# DualMonoPSU3.net
KiCad netlist of a schematic drawn in EAGLE
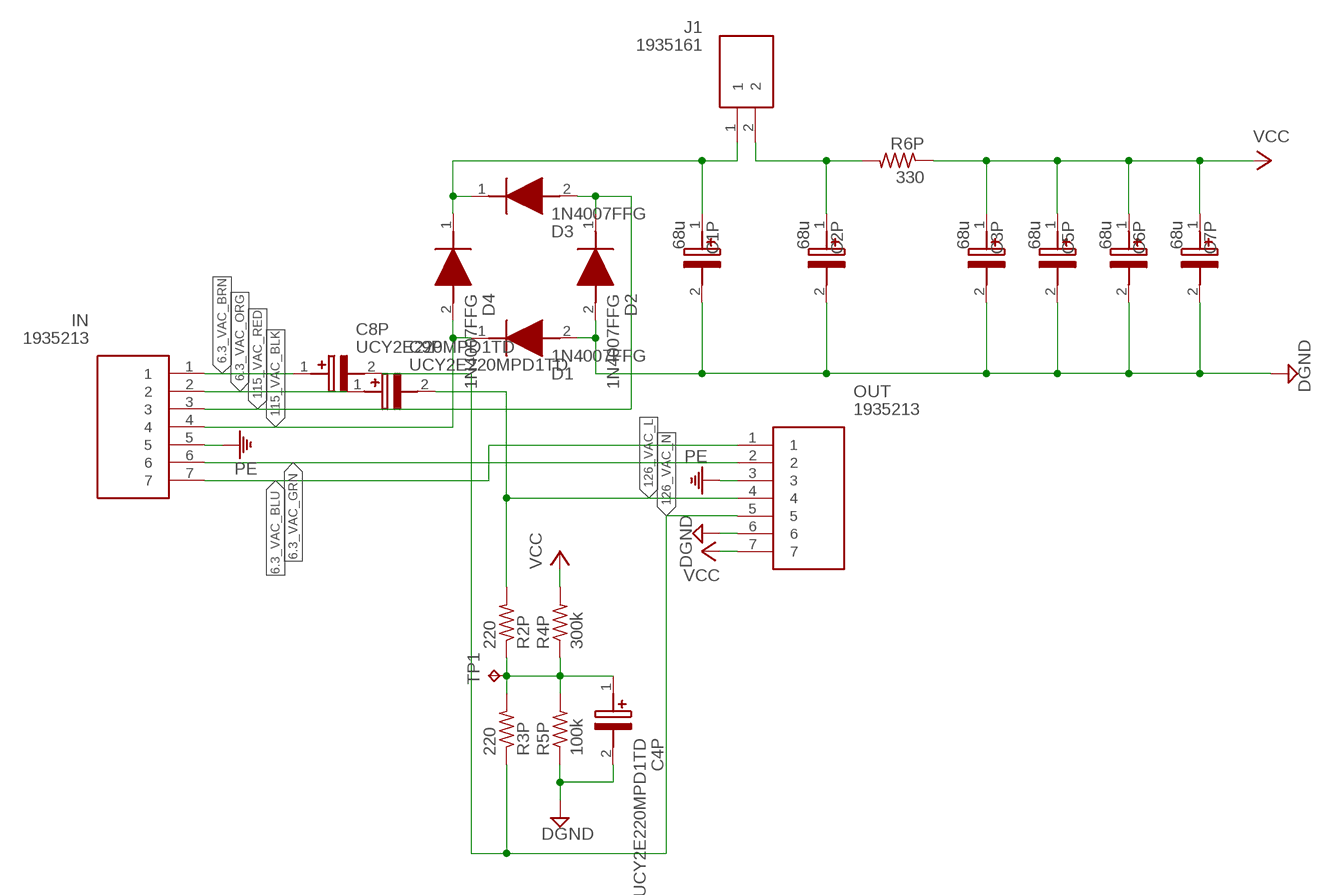
[diagram p0: schematic, sheet 1]

(export (version "E")
  (design (tool "Eeschema 10.0.6"))
  (components
    (comp (ref "C1P")
      (value "68u")
      (footprint "eagle-import:CAPPRD750W80D1475H4700")
      (fields (field (name "MANUFACTURER_PART_NUMBER") "500HXW68MEFR14.5X45"))
      (libsource (lib "eagle-import") (part "500HXW68MEFR14.5X45"))
    )
    (comp (ref "C2P")
      (value "68u")
      (footprint "eagle-import:CAPPRD750W80D1475H4700")
      (fields (field (name "MANUFACTURER_PART_NUMBER") "500HXW68MEFR14.5X45"))
      (libsource (lib "eagle-import") (part "500HXW68MEFR14.5X45"))
    )
    (comp (ref "C3P")
      (value "68u")
      (footprint "eagle-import:CAPPRD750W80D1475H4700")
      (fields (field (name "MANUFACTURER_PART_NUMBER") "500HXW68MEFR14.5X45"))
      (libsource (lib "eagle-import") (part "500HXW68MEFR14.5X45"))
    )
    (comp (ref "C4P")
      (value "UCY2E220MPD1TD")
      (footprint "eagle-import:CAPPRD500W60D1025H1750")
      (fields (field (name "MOUSER_PART_NUMBER") "647-UCY2E220MPD1TD"))
      (libsource (lib "eagle-import") (part "UCY2E220MPD1TD"))
    )
    (comp (ref "C5P")
      (value "68u")
      (footprint "eagle-import:CAPPRD750W80D1475H4700")
      (fields (field (name "MANUFACTURER_PART_NUMBER") "500HXW68MEFR14.5X45"))
      (libsource (lib "eagle-import") (part "500HXW68MEFR14.5X45"))
    )
    (comp (ref "C6P")
      (value "68u")
      (footprint "eagle-import:CAPPRD750W80D1475H4700")
      (fields (field (name "MANUFACTURER_PART_NUMBER") "500HXW68MEFR14.5X45"))
      (libsource (lib "eagle-import") (part "500HXW68MEFR14.5X45"))
    )
    (comp (ref "C7P")
      (value "68u")
      (footprint "eagle-import:CAPPRD750W80D1475H4700")
      (fields (field (name "MANUFACTURER_PART_NUMBER") "500HXW68MEFR14.5X45"))
      (libsource (lib "eagle-import") (part "500HXW68MEFR14.5X45"))
    )
    (comp (ref "C8P")
      (value "UCY2E220MPD1TD")
      (footprint "eagle-import:CAPPRD500W60D1025H1750")
      (fields (field (name "MOUSER_PART_NUMBER") "647-UCY2E220MPD1TD"))
      (libsource (lib "eagle-import") (part "UCY2E220MPD1TD"))
    )
    (comp (ref "C9P")
      (value "UCY2E220MPD1TD")
      (footprint "eagle-import:CAPPRD500W60D1025H1750")
      (fields (field (name "MOUSER_PART_NUMBER") "647-UCY2E220MPD1TD"))
      (libsource (lib "eagle-import") (part "UCY2E220MPD1TD"))
    )
    (comp (ref "D1")
      (value "1N4007FFG")
      (footprint "eagle-import:DIOAD1405W86L465D235")
      (fields (field (name "MOUSER_PART_NUMBER") "863-1N4007FFG"))
      (libsource (lib "eagle-import") (part "1N4007FFG"))
    )
    (comp (ref "D2")
      (value "1N4007FFG")
      (footprint "eagle-import:DIOAD1405W86L465D235")
      (fields (field (name "MOUSER_PART_NUMBER") "863-1N4007FFG"))
      (libsource (lib "eagle-import") (part "1N4007FFG"))
    )
    (comp (ref "D3")
      (value "1N4007FFG")
      (footprint "eagle-import:DIOAD1405W86L465D235")
      (fields (field (name "MOUSER_PART_NUMBER") "863-1N4007FFG"))
      (libsource (lib "eagle-import") (part "1N4007FFG"))
    )
    (comp (ref "D4")
      (value "1N4007FFG")
      (footprint "eagle-import:DIOAD1405W86L465D235")
      (fields (field (name "MOUSER_PART_NUMBER") "863-1N4007FFG"))
      (libsource (lib "eagle-import") (part "1N4007FFG"))
    )
    (comp (ref "IN")
      (value "1935213")
      (footprint "eagle-import:1935213")
      (fields (field (name "MOUSER_PART_NUMBER") "651-1935213"))
      (libsource (lib "eagle-import") (part "1935213"))
    )
    (comp (ref "J1")
      (value "1935161")
      (footprint "eagle-import:1935161")
      (fields (field (name "MOUSER_PART_NUMBER") "651-1935161"))
      (libsource (lib "eagle-import") (part "1935161"))
    )
    (comp (ref "OUT")
      (value "1935213")
      (footprint "eagle-import:1935213")
      (fields (field (name "MOUSER_PART_NUMBER") "651-1935213"))
      (libsource (lib "eagle-import") (part "1935213"))
    )
    (comp (ref "R2P")
      (value "220")
      (footprint "eagle-import:0411_15")
      (libsource (lib "eagle-import") (part "R-US_0411/15"))
    )
    (comp (ref "R3P")
      (value "220")
      (footprint "eagle-import:0411_15")
      (libsource (lib "eagle-import") (part "R-US_0411/15"))
    )
    (comp (ref "R4P")
      (value "300k")
      (footprint "eagle-import:0411_15")
      (libsource (lib "eagle-import") (part "R-US_0411/15"))
    )
    (comp (ref "R5P")
      (value "100k")
      (footprint "eagle-import:0411_15")
      (libsource (lib "eagle-import") (part "R-US_0411/15"))
    )
    (comp (ref "R6P")
      (value "330")
      (footprint "eagle-import:0411_15")
      (libsource (lib "eagle-import") (part "R-US_0411/15"))
    )
    (comp (ref "TP1")
      (value "TPB2,54")
      (footprint "eagle-import:B2,54")
      (libsource (lib "eagle-import") (part "TPB2,54"))
    )
  )
  (nets
    (net (code "1") (name "6.3_VAC_BLU") (class "Default")
      (node (ref "IN") (pin "7") (pinfunction "7_7") (pintype "bidirectional"))
      (node (ref "OUT") (pin "1") (pinfunction "1_1") (pintype "bidirectional"))
    )
    (net (code "2") (name "6.3_VAC_BRN") (class "Default")
      (node (ref "C8P") (pin "1") (pinfunction "+_1") (pintype "bidirectional"))
      (node (ref "IN") (pin "1") (pinfunction "1_1") (pintype "bidirectional"))
    )
    (net (code "3") (name "6.3_VAC_GRN") (class "Default")
      (node (ref "IN") (pin "6") (pinfunction "6_6") (pintype "bidirectional"))
      (node (ref "OUT") (pin "2") (pinfunction "2_2") (pintype "bidirectional"))
    )
    (net (code "4") (name "6.3_VAC_ORG") (class "Default")
      (node (ref "C9P") (pin "1") (pinfunction "+_1") (pintype "bidirectional"))
      (node (ref "IN") (pin "2") (pinfunction "2_2") (pintype "bidirectional"))
    )
    (net (code "5") (name "115_VAC_BLK") (class "Default")
      (node (ref "D1") (pin "1") (pinfunction "K_1") (pintype "bidirectional"))
      (node (ref "D4") (pin "2") (pinfunction "A_2") (pintype "bidirectional"))
      (node (ref "IN") (pin "4") (pinfunction "4_4") (pintype "bidirectional"))
    )
    (net (code "6") (name "115_VAC_RED") (class "Default")
      (node (ref "D2") (pin "1") (pinfunction "K_1") (pintype "bidirectional"))
      (node (ref "D3") (pin "2") (pinfunction "A_2") (pintype "bidirectional"))
      (node (ref "IN") (pin "3") (pinfunction "3_3") (pintype "bidirectional"))
    )
    (net (code "7") (name "126_VAC_L") (class "Default")
      (node (ref "C9P") (pin "2") (pinfunction "-_2") (pintype "bidirectional"))
      (node (ref "OUT") (pin "4") (pinfunction "4_4") (pintype "bidirectional"))
      (node (ref "R2P") (pin "2") (pinfunction "2_2") (pintype "passive"))
    )
    (net (code "8") (name "126_VAC_N") (class "Default")
      (node (ref "C8P") (pin "2") (pinfunction "-_2") (pintype "bidirectional"))
      (node (ref "OUT") (pin "5") (pinfunction "5_5") (pintype "bidirectional"))
      (node (ref "R3P") (pin "1") (pinfunction "1_1") (pintype "passive"))
    )
    (net (code "9") (name "DGND") (class "Default")
      (node (ref "C1P") (pin "2") (pinfunction "-_2") (pintype "bidirectional"))
      (node (ref "C2P") (pin "2") (pinfunction "-_2") (pintype "bidirectional"))
      (node (ref "C3P") (pin "2") (pinfunction "-_2") (pintype "bidirectional"))
      (node (ref "C4P") (pin "2") (pinfunction "-_2") (pintype "bidirectional"))
      (node (ref "C5P") (pin "2") (pinfunction "-_2") (pintype "bidirectional"))
      (node (ref "C6P") (pin "2") (pinfunction "-_2") (pintype "bidirectional"))
      (node (ref "C7P") (pin "2") (pinfunction "-_2") (pintype "bidirectional"))
      (node (ref "D1") (pin "2") (pinfunction "A_2") (pintype "bidirectional"))
      (node (ref "D2") (pin "2") (pinfunction "A_2") (pintype "bidirectional"))
      (node (ref "OUT") (pin "6") (pinfunction "6_6") (pintype "bidirectional"))
      (node (ref "R5P") (pin "1") (pinfunction "1_1") (pintype "passive"))
    )
    (net (code "10") (name "Net-(C1P-+)") (class "Default")
      (node (ref "C1P") (pin "1") (pinfunction "+_1") (pintype "bidirectional"))
      (node (ref "D3") (pin "1") (pinfunction "K_1") (pintype "bidirectional"))
      (node (ref "D4") (pin "1") (pinfunction "K_1") (pintype "bidirectional"))
      (node (ref "J1") (pin "1") (pinfunction "1_1") (pintype "bidirectional"))
    )
    (net (code "11") (name "Net-(C2P-+)") (class "Default")
      (node (ref "C2P") (pin "1") (pinfunction "+_1") (pintype "bidirectional"))
      (node (ref "J1") (pin "2") (pinfunction "2_2") (pintype "bidirectional"))
      (node (ref "R6P") (pin "2") (pinfunction "2_2") (pintype "passive"))
    )
    (net (code "12") (name "Net-(C4P-+)") (class "Default")
      (node (ref "C4P") (pin "1") (pinfunction "+_1") (pintype "bidirectional"))
      (node (ref "R2P") (pin "1") (pinfunction "1_1") (pintype "passive"))
      (node (ref "R3P") (pin "2") (pinfunction "2_2") (pintype "passive"))
      (node (ref "R4P") (pin "1") (pinfunction "1_1") (pintype "passive"))
      (node (ref "R5P") (pin "2") (pinfunction "2_2") (pintype "passive"))
      (node (ref "TP1") (pin "TP") (pinfunction "TP_TP") (pintype "input"))
    )
    (net (code "13") (name "PE") (class "Default")
      (node (ref "IN") (pin "5") (pinfunction "5_5") (pintype "bidirectional"))
      (node (ref "OUT") (pin "3") (pinfunction "3_3") (pintype "bidirectional"))
    )
    (net (code "14") (name "VCC") (class "Default")
      (node (ref "C3P") (pin "1") (pinfunction "+_1") (pintype "bidirectional"))
      (node (ref "C5P") (pin "1") (pinfunction "+_1") (pintype "bidirectional"))
      (node (ref "C6P") (pin "1") (pinfunction "+_1") (pintype "bidirectional"))
      (node (ref "C7P") (pin "1") (pinfunction "+_1") (pintype "bidirectional"))
      (node (ref "OUT") (pin "7") (pinfunction "7_7") (pintype "bidirectional"))
      (node (ref "R4P") (pin "2") (pinfunction "2_2") (pintype "passive"))
      (node (ref "R6P") (pin "1") (pinfunction "1_1") (pintype "passive"))
    )
  )
)
